# ioni.net
KiCad netlist of a schematic drawn in Altium Designer
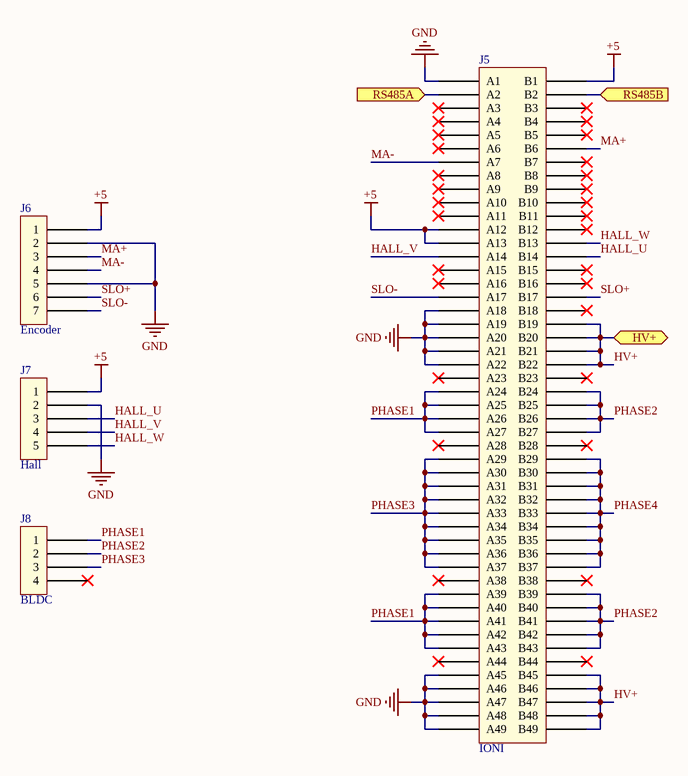
[diagram p0: ioni.SchDoc]

(export (version "E")
  (design (tool "Eeschema 10.0.6"))
  (components
    (comp (ref "J5")
      (value "IONI")
      (footprint "PCB-9n0g0vo7nxv8tvos4xzh-1")
      (description "IONI Motor Controller")
      (libsource (lib "CommunityVault") (part "CMP-gexh7s52tbg9y3x1n92d-1"))
    )
    (comp (ref "J6")
      (value "Encoder")
      (footprint "PCB-c13xtdp0a1wdkl558rz9-1")
      (fields (field (name "MANUFACTURER PART NUMBER") "0533750710"))
      (libsource (lib "CommunityVault") (part "CMP-9d2a54dfa82f42ed-1"))
    )
    (comp (ref "J7")
      (value "Hall")
      (footprint "PCB-83mh4wjdb7t4rba86im5-1")
      (description "2.50mm Pitch Mini-LockT Wire-to-Board Header, Vertical, Friction and Positive Lock, 5 Circuits")
      (fields (field (name "MANUFACTURER PART NUMBER") "53375-0510"))
      (libsource (lib "CommunityVault") (part "CMP-1130547-3"))
    )
    (comp (ref "J8")
      (value "BLDC")
      (footprint "PCB-n62yc6w6j91xslt67wd4-1")
      (description "Mega-Fit Vert Hdr Assy 4 Ckt Tin")
      (fields (field (name "MANUFACTURER PART NUMBER") "0768290004"))
      (libsource (lib "CommunityVault") (part "CMP-ff94357216382053-1"))
    )
  )
  (nets
    (net (code "1") (name "+5") (class "Default")
      (node (ref "J5") (pin "12") (pinfunction "A12_12") (pintype "passive"))
      (node (ref "J5") (pin "13") (pinfunction "A13_13") (pintype "passive"))
      (node (ref "J5") (pin "50") (pinfunction "B1_50") (pintype "passive"))
      (node (ref "J6") (pin "1") (pinfunction "1_1") (pintype "passive"))
      (node (ref "J7") (pin "1") (pinfunction "1_1") (pintype "passive"))
    )
    (net (code "2") (name "/HALL_U") (class "Default")
      (node (ref "J5") (pin "63") (pinfunction "B14_63") (pintype "passive"))
      (node (ref "J7") (pin "3") (pinfunction "3_3") (pintype "passive"))
    )
    (net (code "3") (name "/HALL_V") (class "Default")
      (node (ref "J5") (pin "14") (pinfunction "A14_14") (pintype "passive"))
      (node (ref "J7") (pin "4") (pinfunction "4_4") (pintype "passive"))
    )
    (net (code "4") (name "/HALL_W") (class "Default")
      (node (ref "J5") (pin "62") (pinfunction "B13_62") (pintype "passive"))
      (node (ref "J7") (pin "5") (pinfunction "5_5") (pintype "passive"))
    )
    (net (code "5") (name "/HV+") (class "Default")
      (node (ref "J5") (pin "68") (pinfunction "B19_68") (pintype "passive"))
      (node (ref "J5") (pin "69") (pinfunction "B20_69") (pintype "passive"))
      (node (ref "J5") (pin "70") (pinfunction "B21_70") (pintype "passive"))
      (node (ref "J5") (pin "71") (pinfunction "B22_71") (pintype "passive"))
      (node (ref "J5") (pin "94") (pinfunction "B45_94") (pintype "passive"))
      (node (ref "J5") (pin "95") (pinfunction "B46_95") (pintype "passive"))
      (node (ref "J5") (pin "96") (pinfunction "B47_96") (pintype "passive"))
      (node (ref "J5") (pin "97") (pinfunction "B48_97") (pintype "passive"))
      (node (ref "J5") (pin "98") (pinfunction "B49_98") (pintype "passive"))
    )
    (net (code "6") (name "/MA+") (class "Default")
      (node (ref "J5") (pin "55") (pinfunction "B6_55") (pintype "passive"))
      (node (ref "J6") (pin "3") (pinfunction "3_3") (pintype "passive"))
    )
    (net (code "7") (name "/MA-") (class "Default")
      (node (ref "J5") (pin "7") (pinfunction "A7_7") (pintype "passive"))
      (node (ref "J6") (pin "4") (pinfunction "4_4") (pintype "passive"))
    )
    (net (code "8") (name "/PHASE1") (class "Default")
      (node (ref "J5") (pin "24") (pinfunction "A24_24") (pintype "passive"))
      (node (ref "J5") (pin "25") (pinfunction "A25_25") (pintype "passive"))
      (node (ref "J5") (pin "26") (pinfunction "A26_26") (pintype "passive"))
      (node (ref "J5") (pin "27") (pinfunction "A27_27") (pintype "passive"))
      (node (ref "J5") (pin "39") (pinfunction "A39_39") (pintype "passive"))
      (node (ref "J5") (pin "40") (pinfunction "A40_40") (pintype "passive"))
      (node (ref "J5") (pin "41") (pinfunction "A41_41") (pintype "passive"))
      (node (ref "J5") (pin "42") (pinfunction "A42_42") (pintype "passive"))
      (node (ref "J5") (pin "43") (pinfunction "A43_43") (pintype "passive"))
      (node (ref "J8") (pin "1") (pinfunction "1_1") (pintype "passive"))
    )
    (net (code "9") (name "/PHASE2") (class "Default")
      (node (ref "J5") (pin "73") (pinfunction "B24_73") (pintype "passive"))
      (node (ref "J5") (pin "74") (pinfunction "B25_74") (pintype "passive"))
      (node (ref "J5") (pin "75") (pinfunction "B26_75") (pintype "passive"))
      (node (ref "J5") (pin "76") (pinfunction "B27_76") (pintype "passive"))
      (node (ref "J5") (pin "88") (pinfunction "B39_88") (pintype "passive"))
      (node (ref "J5") (pin "89") (pinfunction "B40_89") (pintype "passive"))
      (node (ref "J5") (pin "90") (pinfunction "B41_90") (pintype "passive"))
      (node (ref "J5") (pin "91") (pinfunction "B42_91") (pintype "passive"))
      (node (ref "J5") (pin "92") (pinfunction "B43_92") (pintype "passive"))
      (node (ref "J8") (pin "2") (pinfunction "2_2") (pintype "passive"))
    )
    (net (code "10") (name "/PHASE3") (class "Default")
      (node (ref "J5") (pin "29") (pinfunction "A29_29") (pintype "passive"))
      (node (ref "J5") (pin "30") (pinfunction "A30_30") (pintype "passive"))
      (node (ref "J5") (pin "31") (pinfunction "A31_31") (pintype "passive"))
      (node (ref "J5") (pin "32") (pinfunction "A32_32") (pintype "passive"))
      (node (ref "J5") (pin "33") (pinfunction "A33_33") (pintype "passive"))
      (node (ref "J5") (pin "34") (pinfunction "A34_34") (pintype "passive"))
      (node (ref "J5") (pin "35") (pinfunction "A35_35") (pintype "passive"))
      (node (ref "J5") (pin "36") (pinfunction "A36_36") (pintype "passive"))
      (node (ref "J5") (pin "37") (pinfunction "A37_37") (pintype "passive"))
      (node (ref "J8") (pin "3") (pinfunction "3_3") (pintype "passive"))
    )
    (net (code "11") (name "/PHASE4") (class "Default")
      (node (ref "J5") (pin "78") (pinfunction "B29_78") (pintype "passive"))
      (node (ref "J5") (pin "79") (pinfunction "B30_79") (pintype "passive"))
      (node (ref "J5") (pin "80") (pinfunction "B31_80") (pintype "passive"))
      (node (ref "J5") (pin "81") (pinfunction "B32_81") (pintype "passive"))
      (node (ref "J5") (pin "82") (pinfunction "B33_82") (pintype "passive"))
      (node (ref "J5") (pin "83") (pinfunction "B34_83") (pintype "passive"))
      (node (ref "J5") (pin "84") (pinfunction "B35_84") (pintype "passive"))
      (node (ref "J5") (pin "85") (pinfunction "B36_85") (pintype "passive"))
      (node (ref "J5") (pin "86") (pinfunction "B37_86") (pintype "passive"))
    )
    (net (code "12") (name "/RS485A") (class "Default")
      (node (ref "J5") (pin "2") (pinfunction "A2_2") (pintype "passive"))
    )
    (net (code "13") (name "/RS485B") (class "Default")
      (node (ref "J5") (pin "51") (pinfunction "B2_51") (pintype "passive"))
    )
    (net (code "14") (name "/SLO+") (class "Default")
      (node (ref "J5") (pin "66") (pinfunction "B17_66") (pintype "passive"))
      (node (ref "J6") (pin "6") (pinfunction "6_6") (pintype "passive"))
    )
    (net (code "15") (name "/SLO-") (class "Default")
      (node (ref "J5") (pin "17") (pinfunction "A17_17") (pintype "passive"))
      (node (ref "J6") (pin "7") (pinfunction "7_7") (pintype "passive"))
    )
    (net (code "16") (name "GND") (class "Default")
      (node (ref "J5") (pin "1") (pinfunction "A1_1") (pintype "passive"))
      (node (ref "J5") (pin "18") (pinfunction "A18_18") (pintype "passive"))
      (node (ref "J5") (pin "19") (pinfunction "A19_19") (pintype "passive"))
      (node (ref "J5") (pin "20") (pinfunction "A20_20") (pintype "passive"))
      (node (ref "J5") (pin "21") (pinfunction "A21_21") (pintype "passive"))
      (node (ref "J5") (pin "22") (pinfunction "A22_22") (pintype "passive"))
      (node (ref "J5") (pin "45") (pinfunction "A45_45") (pintype "passive"))
      (node (ref "J5") (pin "46") (pinfunction "A46_46") (pintype "passive"))
      (node (ref "J5") (pin "47") (pinfunction "A47_47") (pintype "passive"))
      (node (ref "J5") (pin "48") (pinfunction "A48_48") (pintype "passive"))
      (node (ref "J5") (pin "49") (pinfunction "A49_49") (pintype "passive"))
      (node (ref "J6") (pin "2") (pinfunction "2_2") (pintype "passive"))
      (node (ref "J6") (pin "5") (pinfunction "5_5") (pintype "passive"))
      (node (ref "J7") (pin "2") (pinfunction "2_2") (pintype "passive"))
    )
    (net (code "17") (name "unconnected-(J5-A3-Pad3)") (class "Default")
      (node (ref "J5") (pin "3") (pinfunction "A3_3") (pintype "passive+no_connect"))
    )
    (net (code "18") (name "unconnected-(J5-A4-Pad4)") (class "Default")
      (node (ref "J5") (pin "4") (pinfunction "A4_4") (pintype "passive+no_connect"))
    )
    (net (code "19") (name "unconnected-(J5-A5-Pad5)") (class "Default")
      (node (ref "J5") (pin "5") (pinfunction "A5_5") (pintype "passive+no_connect"))
    )
    (net (code "20") (name "unconnected-(J5-A6-Pad6)") (class "Default")
      (node (ref "J5") (pin "6") (pinfunction "A6_6") (pintype "passive+no_connect"))
    )
    (net (code "21") (name "unconnected-(J5-A8-Pad8)") (class "Default")
      (node (ref "J5") (pin "8") (pinfunction "A8_8") (pintype "passive+no_connect"))
    )
    (net (code "22") (name "unconnected-(J5-A9-Pad9)") (class "Default")
      (node (ref "J5") (pin "9") (pinfunction "A9_9") (pintype "passive+no_connect"))
    )
    (net (code "23") (name "unconnected-(J5-A10-Pad10)") (class "Default")
      (node (ref "J5") (pin "10") (pinfunction "A10_10") (pintype "passive+no_connect"))
    )
    (net (code "24") (name "unconnected-(J5-A11-Pad11)") (class "Default")
      (node (ref "J5") (pin "11") (pinfunction "A11_11") (pintype "passive+no_connect"))
    )
    (net (code "25") (name "unconnected-(J5-A15-Pad15)") (class "Default")
      (node (ref "J5") (pin "15") (pinfunction "A15_15") (pintype "passive+no_connect"))
    )
    (net (code "26") (name "unconnected-(J5-A16-Pad16)") (class "Default")
      (node (ref "J5") (pin "16") (pinfunction "A16_16") (pintype "passive+no_connect"))
    )
    (net (code "27") (name "unconnected-(J5-A23-Pad23)") (class "Default")
      (node (ref "J5") (pin "23") (pinfunction "A23_23") (pintype "passive+no_connect"))
    )
    (net (code "28") (name "unconnected-(J5-A28-Pad28)") (class "Default")
      (node (ref "J5") (pin "28") (pinfunction "A28_28") (pintype "passive+no_connect"))
    )
    (net (code "29") (name "unconnected-(J5-A38-Pad38)") (class "Default")
      (node (ref "J5") (pin "38") (pinfunction "A38_38") (pintype "passive+no_connect"))
    )
    (net (code "30") (name "unconnected-(J5-A44-Pad44)") (class "Default")
      (node (ref "J5") (pin "44") (pinfunction "A44_44") (pintype "passive+no_connect"))
    )
    (net (code "31") (name "unconnected-(J5-B3-Pad52)") (class "Default")
      (node (ref "J5") (pin "52") (pinfunction "B3_52") (pintype "passive+no_connect"))
    )
    (net (code "32") (name "unconnected-(J5-B4-Pad53)") (class "Default")
      (node (ref "J5") (pin "53") (pinfunction "B4_53") (pintype "passive+no_connect"))
    )
    (net (code "33") (name "unconnected-(J5-B5-Pad54)") (class "Default")
      (node (ref "J5") (pin "54") (pinfunction "B5_54") (pintype "passive+no_connect"))
    )
    (net (code "34") (name "unconnected-(J5-B7-Pad56)") (class "Default")
      (node (ref "J5") (pin "56") (pinfunction "B7_56") (pintype "passive+no_connect"))
    )
    (net (code "35") (name "unconnected-(J5-B8-Pad57)") (class "Default")
      (node (ref "J5") (pin "57") (pinfunction "B8_57") (pintype "passive+no_connect"))
    )
    (net (code "36") (name "unconnected-(J5-B9-Pad58)") (class "Default")
      (node (ref "J5") (pin "58") (pinfunction "B9_58") (pintype "passive+no_connect"))
    )
    (net (code "37") (name "unconnected-(J5-B10-Pad59)") (class "Default")
      (node (ref "J5") (pin "59") (pinfunction "B10_59") (pintype "passive+no_connect"))
    )
    (net (code "38") (name "unconnected-(J5-B11-Pad60)") (class "Default")
      (node (ref "J5") (pin "60") (pinfunction "B11_60") (pintype "passive+no_connect"))
    )
    (net (code "39") (name "unconnected-(J5-B12-Pad61)") (class "Default")
      (node (ref "J5") (pin "61") (pinfunction "B12_61") (pintype "passive+no_connect"))
    )
    (net (code "40") (name "unconnected-(J5-B15-Pad64)") (class "Default")
      (node (ref "J5") (pin "64") (pinfunction "B15_64") (pintype "passive+no_connect"))
    )
    (net (code "41") (name "unconnected-(J5-B16-Pad65)") (class "Default")
      (node (ref "J5") (pin "65") (pinfunction "B16_65") (pintype "passive+no_connect"))
    )
    (net (code "42") (name "unconnected-(J5-B18-Pad67)") (class "Default")
      (node (ref "J5") (pin "67") (pinfunction "B18_67") (pintype "passive+no_connect"))
    )
    (net (code "43") (name "unconnected-(J5-B23-Pad72)") (class "Default")
      (node (ref "J5") (pin "72") (pinfunction "B23_72") (pintype "passive+no_connect"))
    )
    (net (code "44") (name "unconnected-(J5-B28-Pad77)") (class "Default")
      (node (ref "J5") (pin "77") (pinfunction "B28_77") (pintype "passive+no_connect"))
    )
    (net (code "45") (name "unconnected-(J5-B38-Pad87)") (class "Default")
      (node (ref "J5") (pin "87") (pinfunction "B38_87") (pintype "passive+no_connect"))
    )
    (net (code "46") (name "unconnected-(J5-B44-Pad93)") (class "Default")
      (node (ref "J5") (pin "93") (pinfunction "B44_93") (pintype "passive+no_connect"))
    )
    (net (code "47") (name "unconnected-(J8-Pad4)") (class "Default")
      (node (ref "J8") (pin "4") (pinfunction "4_4") (pintype "passive+no_connect"))
    )
  )
)
